# RC_Servo.net
KiCad netlist of a schematic drawn in Altium Designer
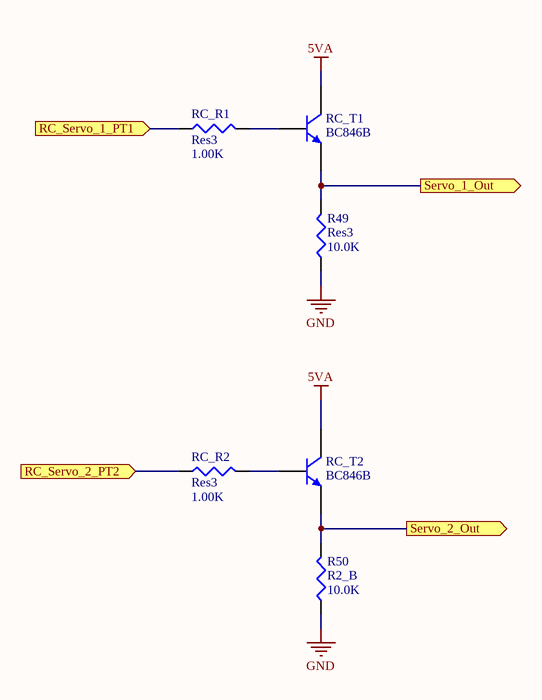
[diagram p0: RC_Servo_.SchDoc]

(export (version "E")
  (design (tool "Eeschema 10.0.6"))
  (components
    (comp (ref "R49")
      (value "Res3")
      (footprint "RESC2112X05M")
      (description "RES SMD 10.0K OHM 1% 1/8W 0805")
      (fields (field (name "ALTIUM_VALUE") "10.0K") (field (name "MPN") "CRCW080510K0FKEA"))
      (libsource (lib "esd_library") (part "Resistor_10.0K"))
    )
    (comp (ref "R50")
      (value "R2_B")
      (footprint "RESC2112X05M")
      (description "RES SMD 10.0K OHM 1% 1/8W 0805")
      (fields (field (name "ALTIUM_VALUE") "10.0K") (field (name "MPN") "CRCW080510K0FKEA"))
      (libsource (lib "esd_library") (part "Resistor_10.0K"))
    )
    (comp (ref "RC_R1")
      (value "Res3")
      (footprint "RESC2112X05M")
      (description "RES SMD 1.00K OHM 1% 1/8W 0805")
      (fields (field (name "ALTIUM_VALUE") "1.00K") (field (name "MPN") "CRCW08051K00FKEA"))
      (libsource (lib "esd_library") (part "Resistor_1.00K"))
    )
    (comp (ref "RC_R2")
      (value "Res3")
      (footprint "RESC2112X05M")
      (description "RES SMD 1.00K OHM 1% 1/8W 0805")
      (fields (field (name "ALTIUM_VALUE") "1.00K") (field (name "MPN") "CRCW08051K00FKEA"))
      (libsource (lib "esd_library") (part "Resistor_1.00K"))
    )
    (comp (ref "RC_T1")
      (value "BC846B")
      (footprint "SOT95P230X110-3M")
      (description "NPN General Purpose Amplifier")
      (libsource (lib "esd_library") (part "BC846B"))
    )
    (comp (ref "RC_T2")
      (value "BC846B")
      (footprint "SOT95P230X110-3M")
      (description "NPN General Purpose Amplifier")
      (libsource (lib "esd_library") (part "BC846B"))
    )
  )
  (nets
    (net (code "1") (name "/RC_Servo_1_PT1") (class "Default")
      (node (ref "RC_R1") (pin "1") (pinfunction "1_1") (pintype "passive"))
    )
    (net (code "2") (name "/RC_Servo_2_PT2") (class "Default")
      (node (ref "RC_R2") (pin "1") (pinfunction "1_1") (pintype "passive"))
    )
    (net (code "3") (name "/Servo_1_Out") (class "Default")
      (node (ref "R49") (pin "2") (pinfunction "2_2") (pintype "passive"))
      (node (ref "RC_T1") (pin "2") (pinfunction "E_2") (pintype "passive"))
    )
    (net (code "4") (name "/Servo_2_Out") (class "Default")
      (node (ref "R50") (pin "2") (pinfunction "2_2") (pintype "passive"))
      (node (ref "RC_T2") (pin "2") (pinfunction "E_2") (pintype "passive"))
    )
    (net (code "5") (name "5VA") (class "Default")
      (node (ref "RC_T1") (pin "3") (pinfunction "C_3") (pintype "passive"))
      (node (ref "RC_T2") (pin "3") (pinfunction "C_3") (pintype "passive"))
    )
    (net (code "6") (name "GND") (class "Default")
      (node (ref "R49") (pin "1") (pinfunction "1_1") (pintype "passive"))
      (node (ref "R50") (pin "1") (pinfunction "1_1") (pintype "passive"))
    )
    (net (code "7") (name "Net-(RC_T1-B)") (class "Default")
      (node (ref "RC_R1") (pin "2") (pinfunction "2_2") (pintype "passive"))
      (node (ref "RC_T1") (pin "1") (pinfunction "B_1") (pintype "passive"))
    )
    (net (code "8") (name "Net-(RC_T2-B)") (class "Default")
      (node (ref "RC_R2") (pin "2") (pinfunction "2_2") (pintype "passive"))
      (node (ref "RC_T2") (pin "1") (pinfunction "B_1") (pintype "passive"))
    )
  )
)
